# MCU.net
KiCad netlist of a schematic drawn in Altium Designer
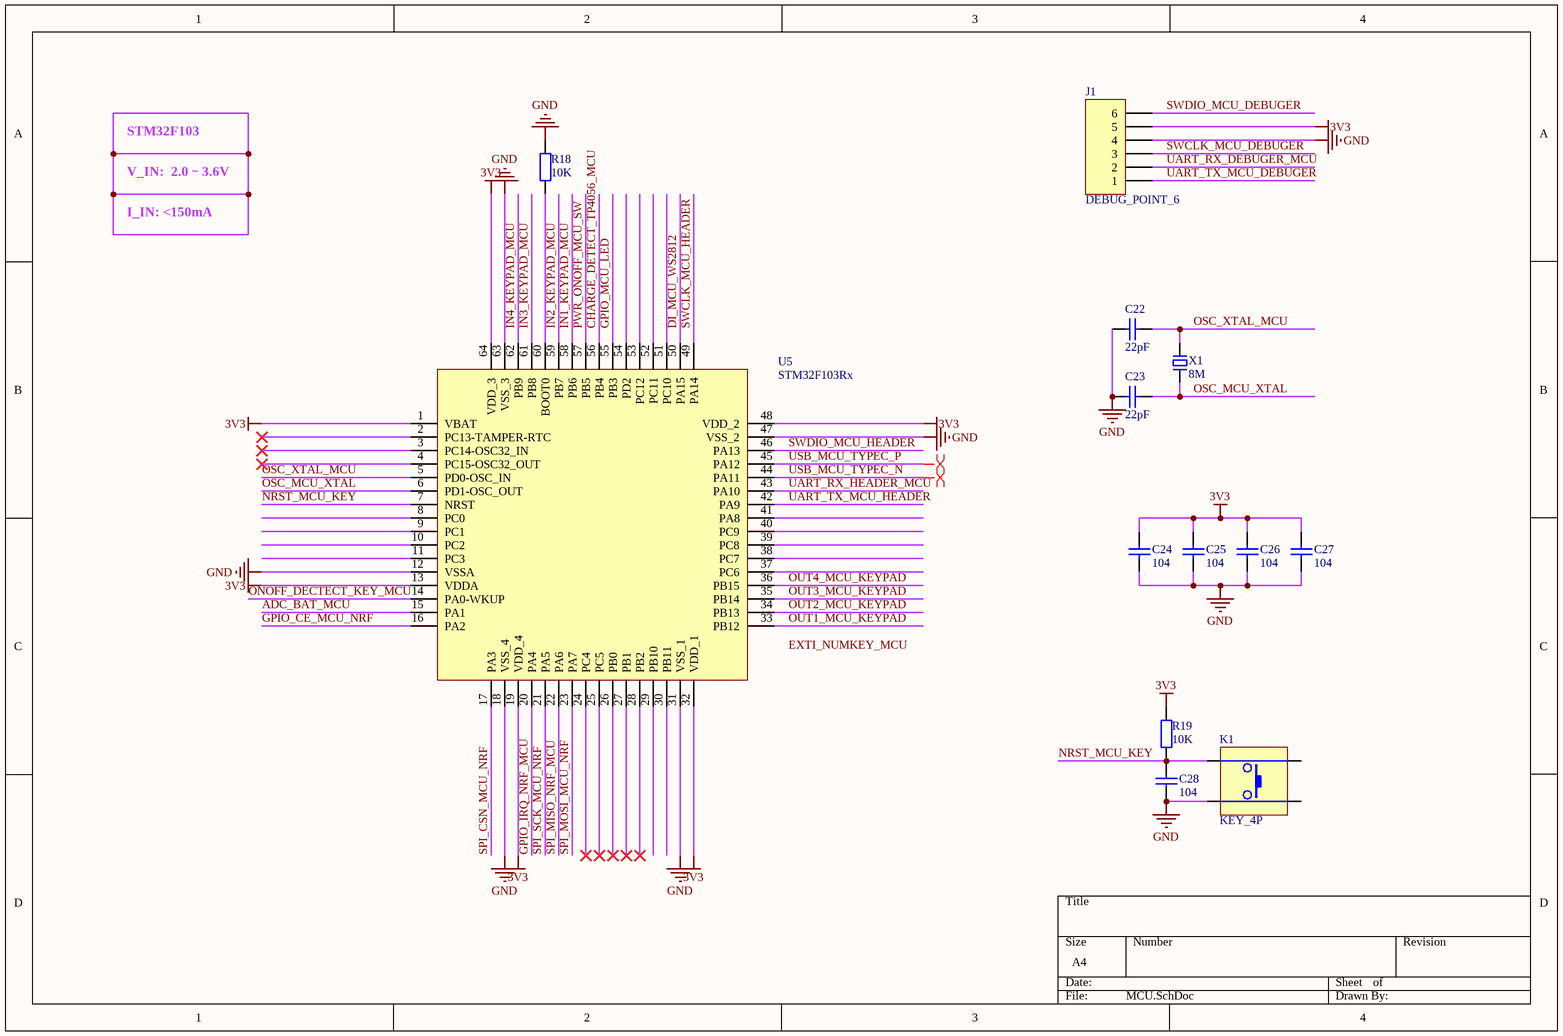
[diagram p0: MCU.SchDoc]

(export (version "E")
  (design (tool "Eeschema 10.0.6"))
  (components
    (comp (ref "C22")
      (value "22pF")
      (footprint "Cap-0603")
      (description "贴片陶瓷电容")
      (libsource (lib "Miscellaneous Base") (part "CAP"))
    )
    (comp (ref "C23")
      (value "22pF")
      (footprint "Cap-0603")
      (description "贴片陶瓷电容")
      (libsource (lib "Miscellaneous Base") (part "CAP"))
    )
    (comp (ref "C24")
      (value "104")
      (footprint "Cap-0603")
      (description "贴片陶瓷电容")
      (libsource (lib "Miscellaneous Base") (part "CAP"))
    )
    (comp (ref "C25")
      (value "104")
      (footprint "Cap-0603")
      (description "贴片陶瓷电容")
      (libsource (lib "Miscellaneous Base") (part "CAP"))
    )
    (comp (ref "C26")
      (value "104")
      (footprint "Cap-0603")
      (description "贴片陶瓷电容")
      (libsource (lib "Miscellaneous Base") (part "CAP"))
    )
    (comp (ref "C27")
      (value "104")
      (footprint "Cap-0603")
      (description "贴片陶瓷电容")
      (libsource (lib "Miscellaneous Base") (part "CAP"))
    )
    (comp (ref "C28")
      (value "104")
      (footprint "Cap-0603")
      (description "贴片陶瓷电容")
      (libsource (lib "Miscellaneous Base") (part "CAP"))
    )
    (comp (ref "J1")
      (value "DEBUG_POINT_6")
      (footprint "DEBUG_POINT_6")
      (libsource (lib "Miscellaneous Others") (part "DEBUG_POINT_6"))
    )
    (comp (ref "K1")
      (value "KEY_4P")
      (footprint "SW-SMD-3X4X2.5")
      (libsource (lib "Miscellaneous Switch") (part "KEY_4P"))
    )
    (comp (ref "R18")
      (value "10K")
      (footprint "Res-0603")
      (description "贴片电阻")
      (libsource (lib "Miscellaneous Base") (part "RES"))
    )
    (comp (ref "R19")
      (value "10K")
      (footprint "Res-0603")
      (description "贴片电阻")
      (libsource (lib "Miscellaneous Base") (part "RES"))
    )
    (comp (ref "U5")
      (value "STM32F103Rx")
      (footprint "STM-LQFP64_N")
      (libsource (lib "Miscellaneous MCU") (part "STM32F103Rx"))
    )
    (comp (ref "X1")
      (value "8M")
      (footprint "OSC 5032-2P")
      (description "2脚无源脚晶振")
      (libsource (lib "Miscellaneous XTAL") (part "XTAL-2P"))
    )
  )
  (nets
    (net (code "1") (name "/ADC_BAT_MCU") (class "Default")
      (node (ref "U5") (pin "15") (pinfunction "PA1_15") (pintype "power_in"))
    )
    (net (code "2") (name "/CHARGE_DETECT_TP4056_MCU") (class "Default")
      (node (ref "U5") (pin "56") (pinfunction "PB4_56") (pintype "power_in"))
    )
    (net (code "3") (name "/DI_MCU_WS2812") (class "Default")
      (node (ref "U5") (pin "50") (pinfunction "PA15_50") (pintype "power_in"))
    )
    (net (code "5") (name "/GPIO_CE_MCU_NRF") (class "Default")
      (node (ref "U5") (pin "16") (pinfunction "PA2_16") (pintype "power_in"))
    )
    (net (code "6") (name "/GPIO_IRQ_NRF_MCU") (class "Default")
      (node (ref "U5") (pin "20") (pinfunction "PA4_20") (pintype "power_in"))
    )
    (net (code "7") (name "/GPIO_MCU_LED") (class "Default")
      (node (ref "U5") (pin "55") (pinfunction "PB3_55") (pintype "power_in"))
    )
    (net (code "8") (name "/IN1_KEYPAD_MCU") (class "Default")
      (node (ref "U5") (pin "58") (pinfunction "PB6_58") (pintype "power_in"))
    )
    (net (code "9") (name "/IN2_KEYPAD_MCU") (class "Default")
      (node (ref "U5") (pin "59") (pinfunction "PB7_59") (pintype "power_in"))
    )
    (net (code "10") (name "/IN3_KEYPAD_MCU") (class "Default")
      (node (ref "U5") (pin "61") (pinfunction "PB8_61") (pintype "power_in"))
    )
    (net (code "11") (name "/IN4_KEYPAD_MCU") (class "Default")
      (node (ref "U5") (pin "62") (pinfunction "PB9_62") (pintype "power_in"))
    )
    (net (code "12") (name "/NRST_MCU_KEY") (class "Default")
      (node (ref "C28") (pin "2") (pinfunction "2_2") (pintype "passive"))
      (node (ref "K1") (pin "3") (pinfunction "3_3") (pintype "passive"))
      (node (ref "R19") (pin "1") (pinfunction "1_1") (pintype "passive"))
      (node (ref "U5") (pin "7") (pinfunction "NRST_7") (pintype "power_in"))
    )
    (net (code "13") (name "/ONOFF_DECTECT_KEY_MCU") (class "Default")
      (node (ref "U5") (pin "14") (pinfunction "PA0-WKUP_14") (pintype "power_in"))
    )
    (net (code "14") (name "/OSC_MCU_XTAL") (class "Default")
      (node (ref "C23") (pin "2") (pinfunction "2_2") (pintype "passive"))
      (node (ref "U5") (pin "6") (pinfunction "PD1-OSC_OUT_6") (pintype "power_in"))
      (node (ref "X1") (pin "1") (pinfunction "1_1") (pintype "passive"))
    )
    (net (code "15") (name "/OSC_XTAL_MCU") (class "Default")
      (node (ref "C22") (pin "2") (pinfunction "2_2") (pintype "passive"))
      (node (ref "U5") (pin "5") (pinfunction "PD0-OSC_IN_5") (pintype "power_in"))
      (node (ref "X1") (pin "2") (pinfunction "2_2") (pintype "passive"))
    )
    (net (code "16") (name "/OUT1_MCU_KEYPAD") (class "Default")
      (node (ref "U5") (pin "33") (pinfunction "PB12_33") (pintype "power_in"))
    )
    (net (code "17") (name "/OUT2_MCU_KEYPAD") (class "Default")
      (node (ref "U5") (pin "34") (pinfunction "PB13_34") (pintype "power_in"))
    )
    (net (code "18") (name "/OUT3_MCU_KEYPAD") (class "Default")
      (node (ref "U5") (pin "35") (pinfunction "PB14_35") (pintype "power_in"))
    )
    (net (code "19") (name "/OUT4_MCU_KEYPAD") (class "Default")
      (node (ref "U5") (pin "36") (pinfunction "PB15_36") (pintype "power_in"))
    )
    (net (code "20") (name "/PWR_ONOFF_MCU_SW") (class "Default")
      (node (ref "U5") (pin "57") (pinfunction "PB5_57") (pintype "power_in"))
    )
    (net (code "21") (name "/SPI_CSN_MCU_NRF") (class "Default")
      (node (ref "U5") (pin "17") (pinfunction "PA3_17") (pintype "power_in"))
    )
    (net (code "22") (name "/SPI_MISO_NRF_MCU") (class "Default")
      (node (ref "U5") (pin "22") (pinfunction "PA6_22") (pintype "power_in"))
    )
    (net (code "23") (name "/SPI_MOSI_MCU_NRF") (class "Default")
      (node (ref "U5") (pin "23") (pinfunction "PA7_23") (pintype "power_in"))
    )
    (net (code "24") (name "/SPI_SCK_MCU_NRF") (class "Default")
      (node (ref "U5") (pin "21") (pinfunction "PA5_21") (pintype "power_in"))
    )
    (net (code "25") (name "/SWCLK_MCU_DEBUGER") (class "Default")
      (node (ref "J1") (pin "3") (pinfunction "3_3") (pintype "passive"))
    )
    (net (code "26") (name "/SWCLK_MCU_HEADER") (class "Default")
      (node (ref "U5") (pin "49") (pinfunction "PA14_49") (pintype "power_in"))
    )
    (net (code "27") (name "/SWDIO_MCU_DEBUGER") (class "Default")
      (node (ref "J1") (pin "6") (pinfunction "6_6") (pintype "passive"))
    )
    (net (code "28") (name "/SWDIO_MCU_HEADER") (class "Default")
      (node (ref "U5") (pin "46") (pinfunction "PA13_46") (pintype "power_in"))
    )
    (net (code "29") (name "/UART_RX_DEBUGER_MCU") (class "Default")
      (node (ref "J1") (pin "2") (pinfunction "2_2") (pintype "passive"))
    )
    (net (code "30") (name "/UART_RX_HEADER_MCU") (class "Default")
      (node (ref "U5") (pin "43") (pinfunction "PA10_43") (pintype "power_in"))
    )
    (net (code "31") (name "/UART_TX_MCU_DEBUGER") (class "Default")
      (node (ref "J1") (pin "1") (pinfunction "1_1") (pintype "passive"))
    )
    (net (code "32") (name "/UART_TX_MCU_HEADER") (class "Default")
      (node (ref "U5") (pin "42") (pinfunction "PA9_42") (pintype "power_in"))
    )
    (net (code "33") (name "/USB_MCU_TYPEC_N") (class "Default")
      (node (ref "U5") (pin "44") (pinfunction "PA11_44") (pintype "power_in"))
    )
    (net (code "34") (name "/USB_MCU_TYPEC_P") (class "Default")
      (node (ref "U5") (pin "45") (pinfunction "PA12_45") (pintype "power_in"))
    )
    (net (code "35") (name "3V3") (class "Default")
      (node (ref "C24") (pin "2") (pinfunction "2_2") (pintype "passive"))
      (node (ref "C25") (pin "2") (pinfunction "2_2") (pintype "passive"))
      (node (ref "C26") (pin "2") (pinfunction "2_2") (pintype "passive"))
      (node (ref "C27") (pin "2") (pinfunction "2_2") (pintype "passive"))
      (node (ref "J1") (pin "5") (pinfunction "5_5") (pintype "passive"))
      (node (ref "R19") (pin "2") (pinfunction "2_2") (pintype "passive"))
      (node (ref "U5") (pin "1") (pinfunction "VBAT_1") (pintype "power_in"))
      (node (ref "U5") (pin "13") (pinfunction "VDDA_13") (pintype "power_in"))
      (node (ref "U5") (pin "19") (pinfunction "VDD_4_19") (pintype "power_in"))
      (node (ref "U5") (pin "32") (pinfunction "VDD_1_32") (pintype "power_in"))
      (node (ref "U5") (pin "48") (pinfunction "VDD_2_48") (pintype "power_in"))
      (node (ref "U5") (pin "64") (pinfunction "VDD_3_64") (pintype "power_in"))
    )
    (net (code "36") (name "GND") (class "Default")
      (node (ref "C22") (pin "1") (pinfunction "1_1") (pintype "passive"))
      (node (ref "C23") (pin "1") (pinfunction "1_1") (pintype "passive"))
      (node (ref "C24") (pin "1") (pinfunction "1_1") (pintype "passive"))
      (node (ref "C25") (pin "1") (pinfunction "1_1") (pintype "passive"))
      (node (ref "C26") (pin "1") (pinfunction "1_1") (pintype "passive"))
      (node (ref "C27") (pin "1") (pinfunction "1_1") (pintype "passive"))
      (node (ref "C28") (pin "1") (pinfunction "1_1") (pintype "passive"))
      (node (ref "J1") (pin "4") (pinfunction "4_4") (pintype "passive"))
      (node (ref "K1") (pin "4") (pinfunction "4_4") (pintype "passive"))
      (node (ref "R18") (pin "2") (pinfunction "2_2") (pintype "passive"))
      (node (ref "U5") (pin "12") (pinfunction "VSSA_12") (pintype "power_in"))
      (node (ref "U5") (pin "18") (pinfunction "VSS_4_18") (pintype "power_in"))
      (node (ref "U5") (pin "31") (pinfunction "VSS_1_31") (pintype "power_in"))
      (node (ref "U5") (pin "47") (pinfunction "VSS_2_47") (pintype "power_in"))
      (node (ref "U5") (pin "63") (pinfunction "VSS_3_63") (pintype "power_in"))
    )
    (net (code "37") (name "Net-(U5-BOOT0)") (class "Default")
      (node (ref "R18") (pin "1") (pinfunction "1_1") (pintype "passive"))
      (node (ref "U5") (pin "60") (pinfunction "BOOT0_60") (pintype "power_in"))
    )
    (net (code "38") (name "unconnected-(K1-Pad1)") (class "Default")
      (node (ref "K1") (pin "1") (pinfunction "1_1") (pintype "passive"))
    )
    (net (code "39") (name "unconnected-(K1-Pad2)") (class "Default")
      (node (ref "K1") (pin "2") (pinfunction "2_2") (pintype "passive"))
    )
    (net (code "40") (name "unconnected-(U5-PA8-Pad41)") (class "Default")
      (node (ref "U5") (pin "41") (pinfunction "PA8_41") (pintype "power_in"))
    )
    (net (code "41") (name "unconnected-(U5-PB0-Pad26)") (class "Default")
      (node (ref "U5") (pin "26") (pinfunction "PB0_26") (pintype "power_in+no_connect"))
    )
    (net (code "42") (name "unconnected-(U5-PB1-Pad27)") (class "Default")
      (node (ref "U5") (pin "27") (pinfunction "PB1_27") (pintype "power_in+no_connect"))
    )
    (net (code "43") (name "unconnected-(U5-PB2-Pad28)") (class "Default")
      (node (ref "U5") (pin "28") (pinfunction "PB2_28") (pintype "power_in+no_connect"))
    )
    (net (code "44") (name "unconnected-(U5-PB10-Pad29)") (class "Default")
      (node (ref "U5") (pin "29") (pinfunction "PB10_29") (pintype "power_in"))
    )
    (net (code "45") (name "unconnected-(U5-PB11-Pad30)") (class "Default")
      (node (ref "U5") (pin "30") (pinfunction "PB11_30") (pintype "power_in"))
    )
    (net (code "46") (name "unconnected-(U5-PC0-Pad8)") (class "Default")
      (node (ref "U5") (pin "8") (pinfunction "PC0_8") (pintype "power_in"))
    )
    (net (code "47") (name "unconnected-(U5-PC1-Pad9)") (class "Default")
      (node (ref "U5") (pin "9") (pinfunction "PC1_9") (pintype "power_in"))
    )
    (net (code "48") (name "unconnected-(U5-PC2-Pad10)") (class "Default")
      (node (ref "U5") (pin "10") (pinfunction "PC2_10") (pintype "power_in"))
    )
    (net (code "49") (name "unconnected-(U5-PC3-Pad11)") (class "Default")
      (node (ref "U5") (pin "11") (pinfunction "PC3_11") (pintype "power_in"))
    )
    (net (code "50") (name "unconnected-(U5-PC4-Pad24)") (class "Default")
      (node (ref "U5") (pin "24") (pinfunction "PC4_24") (pintype "power_in+no_connect"))
    )
    (net (code "51") (name "unconnected-(U5-PC5-Pad25)") (class "Default")
      (node (ref "U5") (pin "25") (pinfunction "PC5_25") (pintype "power_in+no_connect"))
    )
    (net (code "52") (name "unconnected-(U5-PC6-Pad37)") (class "Default")
      (node (ref "U5") (pin "37") (pinfunction "PC6_37") (pintype "power_in"))
    )
    (net (code "53") (name "unconnected-(U5-PC7-Pad38)") (class "Default")
      (node (ref "U5") (pin "38") (pinfunction "PC7_38") (pintype "power_in"))
    )
    (net (code "54") (name "unconnected-(U5-PC8-Pad39)") (class "Default")
      (node (ref "U5") (pin "39") (pinfunction "PC8_39") (pintype "power_in"))
    )
    (net (code "55") (name "unconnected-(U5-PC9-Pad40)") (class "Default")
      (node (ref "U5") (pin "40") (pinfunction "PC9_40") (pintype "power_in"))
    )
    (net (code "56") (name "unconnected-(U5-PC10-Pad51)") (class "Default")
      (node (ref "U5") (pin "51") (pinfunction "PC10_51") (pintype "power_in"))
    )
    (net (code "57") (name "unconnected-(U5-PC11-Pad52)") (class "Default")
      (node (ref "U5") (pin "52") (pinfunction "PC11_52") (pintype "power_in"))
    )
    (net (code "58") (name "unconnected-(U5-PC12-Pad53)") (class "Default")
      (node (ref "U5") (pin "53") (pinfunction "PC12_53") (pintype "power_in"))
    )
    (net (code "59") (name "unconnected-(U5-PC13-TAMPER-RTC-Pad2)") (class "Default")
      (node (ref "U5") (pin "2") (pinfunction "PC13-TAMPER-RTC_2") (pintype "power_in+no_connect"))
    )
    (net (code "60") (name "unconnected-(U5-PC14-OSC32_IN-Pad3)") (class "Default")
      (node (ref "U5") (pin "3") (pinfunction "PC14-OSC32_IN_3") (pintype "power_in+no_connect"))
    )
    (net (code "61") (name "unconnected-(U5-PC15-OSC32_OUT-Pad4)") (class "Default")
      (node (ref "U5") (pin "4") (pinfunction "PC15-OSC32_OUT_4") (pintype "power_in+no_connect"))
    )
    (net (code "62") (name "unconnected-(U5-PD2-Pad54)") (class "Default")
      (node (ref "U5") (pin "54") (pinfunction "PD2_54") (pintype "power_in"))
    )
  )
)
